# 05_USART.net
KiCad netlist of a schematic drawn in Altium Designer
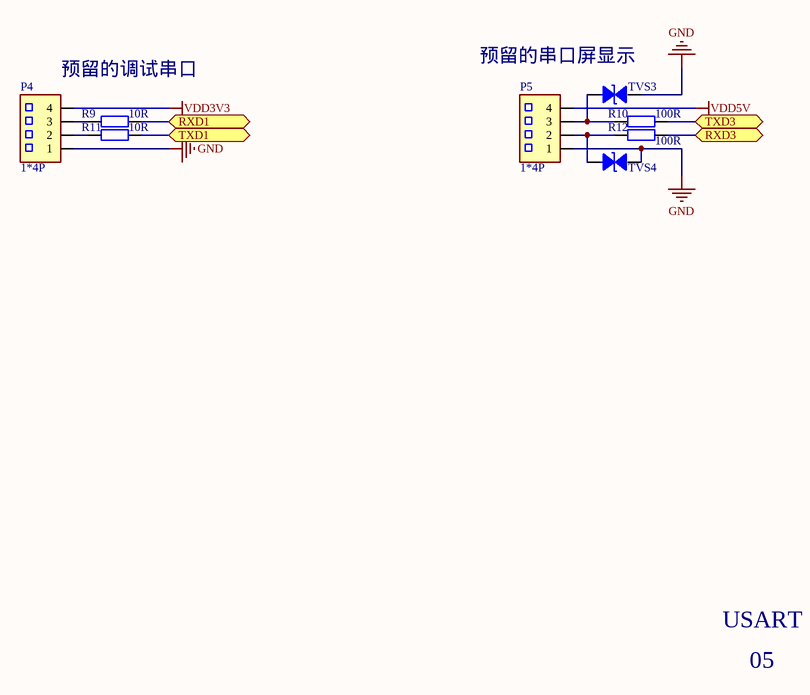
[diagram p0: 05_USART.SchDoc]

(export (version "E")
  (design (tool "Eeschema 10.0.6"))
  (components
    (comp (ref "P4") (value "1*4P") (footprint "XH2.54-4A") (libsource (lib "PARK-N5 V1.0") (part "HDR1*4")))
    (comp (ref "P5") (value "1*4P") (footprint "XH2.54-4A") (libsource (lib "PARK-N5 V1.0") (part "HDR1*4")))
    (comp (ref "R9")
      (value "10R")
      (footprint "SMD-0603")
      (description "贴片电阻 5%")
      (libsource (lib "XiaoyI") (part "RES2"))
    )
    (comp (ref "R10")
      (value "100R")
      (footprint "SMD-0603")
      (description "贴片电阻 5%")
      (libsource (lib "XiaoyI") (part "RES2"))
    )
    (comp (ref "R11")
      (value "10R")
      (footprint "SMD-0603")
      (description "贴片电阻 5%")
      (libsource (lib "XiaoyI") (part "RES2"))
    )
    (comp (ref "R12")
      (value "100R")
      (footprint "SMD-0603")
      (description "贴片电阻 5%")
      (libsource (lib "XiaoyI") (part "RES2"))
    )
    (comp (ref "TVS3")
      (value "ESD5Z5.0CT1G")
      (footprint "SOD-523")
      (description "TVS")
      (libsource (lib "XiaoyI") (part "TVS-1"))
    )
    (comp (ref "TVS4")
      (value "ESD5Z5.0CT1G")
      (footprint "SOD-523")
      (description "TVS")
      (libsource (lib "XiaoyI") (part "TVS-1"))
    )
  )
  (nets
    (net (code "1") (name "/RXD1") (class "Default")
      (node (ref "R9") (pin "2") (pinfunction "2_2") (pintype "passive"))
    )
    (net (code "2") (name "/RXD3") (class "Default")
      (node (ref "R12") (pin "2") (pinfunction "2_2") (pintype "passive"))
    )
    (net (code "3") (name "/TXD1") (class "Default")
      (node (ref "R11") (pin "2") (pinfunction "2_2") (pintype "passive"))
    )
    (net (code "4") (name "/TXD3") (class "Default")
      (node (ref "R10") (pin "2") (pinfunction "2_2") (pintype "passive"))
    )
    (net (code "5") (name "GND") (class "Default")
      (node (ref "P4") (pin "1") (pinfunction "1_1") (pintype "passive"))
      (node (ref "P5") (pin "1") (pinfunction "1_1") (pintype "passive"))
      (node (ref "TVS3") (pin "1") (pinfunction "A_1") (pintype "passive"))
      (node (ref "TVS4") (pin "1") (pinfunction "A_1") (pintype "passive"))
    )
    (net (code "6") (name "Net-(P4-Pad2)") (class "Default")
      (node (ref "P4") (pin "2") (pinfunction "2_2") (pintype "passive"))
      (node (ref "R11") (pin "1") (pinfunction "1_1") (pintype "passive"))
    )
    (net (code "7") (name "Net-(P4-Pad3)") (class "Default")
      (node (ref "P4") (pin "3") (pinfunction "3_3") (pintype "passive"))
      (node (ref "R9") (pin "1") (pinfunction "1_1") (pintype "passive"))
    )
    (net (code "8") (name "Net-(TVS3-B)") (class "Default")
      (node (ref "P5") (pin "3") (pinfunction "3_3") (pintype "passive"))
      (node (ref "R10") (pin "1") (pinfunction "1_1") (pintype "passive"))
      (node (ref "TVS3") (pin "2") (pinfunction "B_2") (pintype "passive"))
    )
    (net (code "9") (name "Net-(TVS4-B)") (class "Default")
      (node (ref "P5") (pin "2") (pinfunction "2_2") (pintype "passive"))
      (node (ref "R12") (pin "1") (pinfunction "1_1") (pintype "passive"))
      (node (ref "TVS4") (pin "2") (pinfunction "B_2") (pintype "passive"))
    )
    (net (code "10") (name "VDD3V3") (class "Default")
      (node (ref "P4") (pin "4") (pinfunction "4_4") (pintype "passive"))
    )
    (net (code "11") (name "VDD5V") (class "Default")
      (node (ref "P5") (pin "4") (pinfunction "4_4") (pintype "passive"))
    )
  )
)
